# Buzzer.net
KiCad netlist of a schematic drawn in Altium Designer
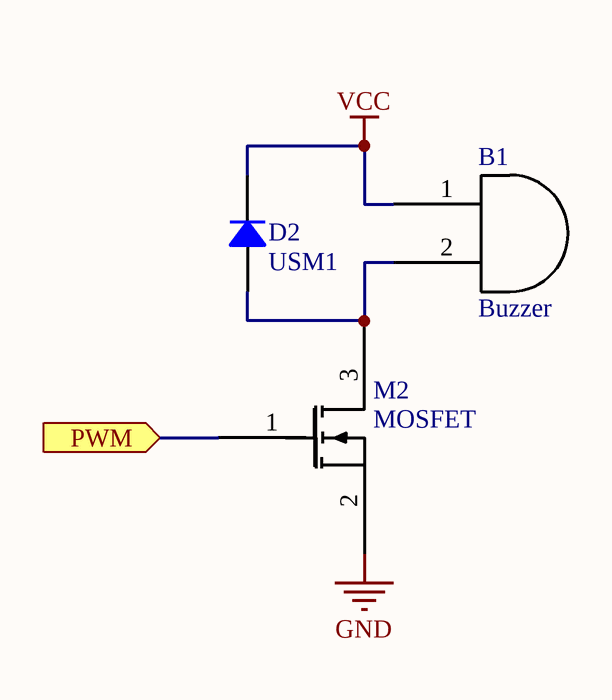
[diagram p0: Buzzer.SchDoc]

(export (version "E")
  (design (tool "Eeschema 10.0.6"))
  (components
    (comp (ref "B1")
      (value "Buzzer")
      (footprint "BUZZER-CSPT12A")
      (libsource (lib "Salman_lib") (part "Buzzer"))
    )
    (comp (ref "D2")
      (value "USM1")
      (footprint "DO-214AC SMA")
      (description "Diode Standard 1000V 1A Surface Mount SMA")
      (fields (field (name "PARTNUMBER") "US1M-13-F"))
      (libsource (lib "Diode") (part "US1M (SMD SMA)"))
    )
    (comp (ref "M2") (value "MOSFET") (footprint "SOT-23") (libsource (lib "Salman_lib") (part "2N7002A")))
  )
  (nets
    (net (code "1") (name "/PWM") (class "Default") (node (ref "M2") (pin "1") (pintype "passive")))
    (net (code "2") (name "GND") (class "Default") (node (ref "M2") (pin "2") (pintype "passive")))
    (net (code "3") (name "Net-(B1-Pad2)") (class "Default")
      (node (ref "B1") (pin "2") (pintype "passive"))
      (node (ref "D2") (pin "1") (pinfunction "1_1") (pintype "passive"))
      (node (ref "M2") (pin "3") (pintype "passive"))
    )
    (net (code "4") (name "VCC") (class "Default")
      (node (ref "B1") (pin "1") (pintype "passive"))
      (node (ref "D2") (pin "2") (pinfunction "2_2") (pintype "passive"))
    )
  )
)
